# Controller.net
KiCad netlist of a schematic drawn in Altium Designer
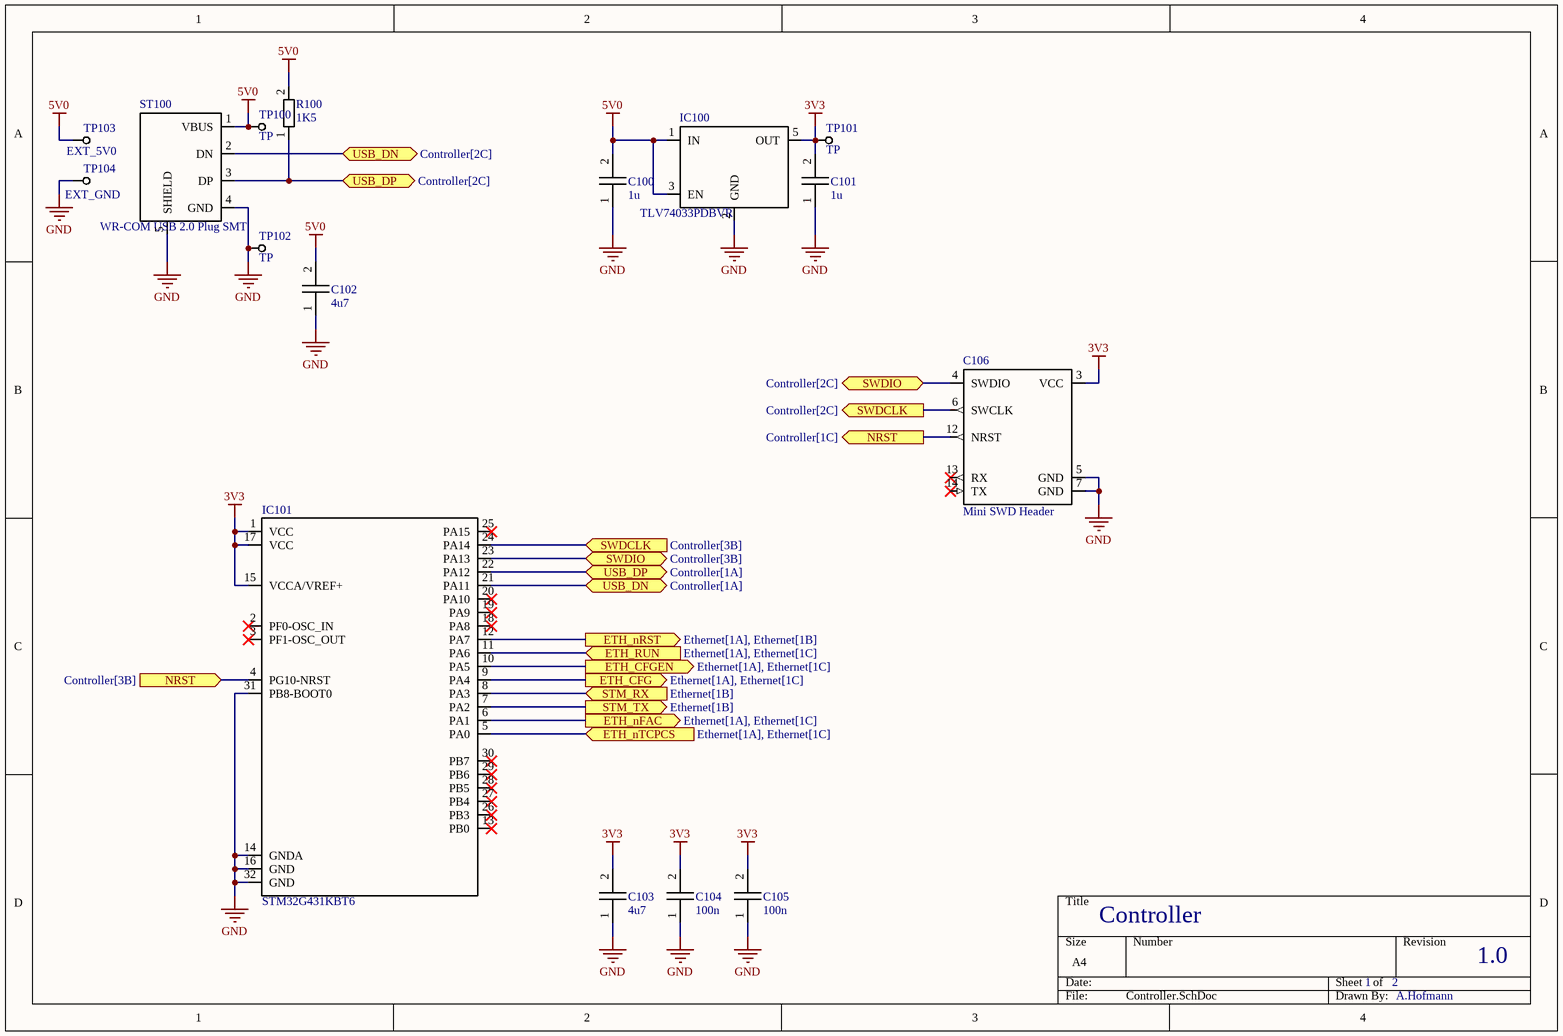
[diagram p0: Controller.SchDoc]

(export (version "E")
  (design (tool "Eeschema 10.0.6"))
  (components
    (comp (ref "C100") (value "1u") (footprint "C_0402") (libsource (lib "wol") (part "CeCa")))
    (comp (ref "C101") (value "1u") (footprint "C_0402") (libsource (lib "wol") (part "CeCa")))
    (comp (ref "C102") (value "4u7") (footprint "C_0603") (libsource (lib "wol") (part "CeCa")))
    (comp (ref "C103") (value "4u7") (footprint "C_0603") (libsource (lib "wol") (part "CeCa")))
    (comp (ref "C104") (value "100n") (footprint "C_0402") (libsource (lib "wol") (part "CeCa")))
    (comp (ref "C105") (value "100n") (footprint "C_0402") (libsource (lib "wol") (part "CeCa")))
    (comp (ref "C106")
      (value "Mini SWD Header")
      (footprint "Mini SWD Header")
      (libsource (lib "wol") (part "Mini SWD Header"))
    )
    (comp (ref "IC100")
      (value "TLV74033PDBVR")
      (footprint "SOT-23")
      (description "Linear Voltage Regulator IC Positive Fixed 1 Output 300mA SOT-23-5")
      (libsource (lib "wol") (part "TLV74033PDBVR"))
    )
    (comp (ref "IC101")
      (value "STM32G431KBT6")
      (footprint "LQFP32")
      (libsource (lib "wol") (part "STM32G431KBT6"))
    )
    (comp (ref "R100") (value "1K5") (footprint "R_0402") (libsource (lib "wol") (part "Res")))
    (comp (ref "ST100")
      (value "WR-COM USB 2.0 Plug SMT")
      (footprint "629004113921")
      (description "CONN PLUG USB2.0 TYPEA 4P SMD RA")
      (libsource (lib "wol") (part "WR-COM USB 2.0 Plug SMT"))
    )
    (comp (ref "TP100") (value "TP") (footprint "STP_0.5mm") (libsource (lib "wol") (part "TP")))
    (comp (ref "TP101") (value "TP") (footprint "STP_0.5mm") (libsource (lib "wol") (part "TP")))
    (comp (ref "TP102") (value "TP") (footprint "STP_0.5mm") (libsource (lib "wol") (part "TP")))
    (comp (ref "TP103") (value "EXT_5V0") (footprint "TTP_1mm") (libsource (lib "wol") (part "TP")))
    (comp (ref "TP104") (value "EXT_GND") (footprint "TTP_1mm") (libsource (lib "wol") (part "TP")))
  )
  (nets
    (net (code "1") (name "/ETH_CFG") (class "Default")
      (node (ref "IC101") (pin "9") (pinfunction "PA4_9") (pintype "bidirectional"))
    )
    (net (code "2") (name "/ETH_CFGEN") (class "Default")
      (node (ref "IC101") (pin "10") (pinfunction "PA5_10") (pintype "bidirectional"))
    )
    (net (code "3") (name "/ETH_RUN") (class "Default")
      (node (ref "IC101") (pin "11") (pinfunction "PA6_11") (pintype "bidirectional"))
    )
    (net (code "4") (name "/ETH_nFAC") (class "Default")
      (node (ref "IC101") (pin "6") (pinfunction "PA1_6") (pintype "bidirectional"))
    )
    (net (code "5") (name "/ETH_nRST") (class "Default")
      (node (ref "IC101") (pin "12") (pinfunction "PA7_12") (pintype "bidirectional"))
    )
    (net (code "6") (name "/ETH_nTCPCS") (class "Default")
      (node (ref "IC101") (pin "5") (pinfunction "PA0_5") (pintype "bidirectional"))
    )
    (net (code "7") (name "/NRST") (class "Default")
      (node (ref "C106") (pin "12") (pinfunction "NRST_12") (pintype "output"))
      (node (ref "IC101") (pin "4") (pinfunction "PG10-NRST_4") (pintype "bidirectional"))
    )
    (net (code "8") (name "/STM_RX") (class "Default")
      (node (ref "IC101") (pin "8") (pinfunction "PA3_8") (pintype "bidirectional"))
    )
    (net (code "9") (name "/STM_TX") (class "Default")
      (node (ref "IC101") (pin "7") (pinfunction "PA2_7") (pintype "bidirectional"))
    )
    (net (code "10") (name "/SWDCLK") (class "Default")
      (node (ref "C106") (pin "6") (pinfunction "SWCLK_6") (pintype "output"))
      (node (ref "IC101") (pin "24") (pinfunction "PA14_24") (pintype "bidirectional"))
    )
    (net (code "11") (name "/SWDIO") (class "Default")
      (node (ref "C106") (pin "4") (pinfunction "SWDIO_4") (pintype "bidirectional"))
      (node (ref "IC101") (pin "23") (pinfunction "PA13_23") (pintype "bidirectional"))
    )
    (net (code "12") (name "/USB_DN") (class "Default")
      (node (ref "IC101") (pin "21") (pinfunction "PA11_21") (pintype "bidirectional"))
      (node (ref "ST100") (pin "2") (pinfunction "DN_2") (pintype "bidirectional"))
    )
    (net (code "13") (name "/USB_DP") (class "Default")
      (node (ref "IC101") (pin "22") (pinfunction "PA12_22") (pintype "bidirectional"))
      (node (ref "R100") (pin "1") (pintype "passive"))
      (node (ref "ST100") (pin "3") (pinfunction "DP_3") (pintype "bidirectional"))
    )
    (net (code "14") (name "3V3") (class "Default")
      (node (ref "C101") (pin "2") (pintype "passive"))
      (node (ref "C103") (pin "2") (pintype "passive"))
      (node (ref "C104") (pin "2") (pintype "passive"))
      (node (ref "C105") (pin "2") (pintype "passive"))
      (node (ref "C106") (pin "3") (pinfunction "VCC_3") (pintype "power_in"))
      (node (ref "IC100") (pin "5") (pinfunction "OUT_5") (pintype "passive"))
      (node (ref "IC101") (pin "1") (pinfunction "VCC_1") (pintype "power_in"))
      (node (ref "IC101") (pin "15") (pinfunction "VCCA/VREF+_15") (pintype "power_in"))
      (node (ref "IC101") (pin "17") (pinfunction "VCC_17") (pintype "power_in"))
      (node (ref "TP101") (pin "1") (pintype "passive"))
    )
    (net (code "15") (name "5V0") (class "Default")
      (node (ref "C100") (pin "2") (pintype "passive"))
      (node (ref "C102") (pin "2") (pintype "passive"))
      (node (ref "IC100") (pin "1") (pinfunction "IN_1") (pintype "passive"))
      (node (ref "IC100") (pin "3") (pinfunction "EN_3") (pintype "passive"))
      (node (ref "R100") (pin "2") (pintype "passive"))
      (node (ref "ST100") (pin "1") (pinfunction "VBUS_1") (pintype "power_in"))
      (node (ref "TP100") (pin "1") (pintype "passive"))
      (node (ref "TP103") (pin "1") (pintype "passive"))
    )
    (net (code "16") (name "GND") (class "Default")
      (node (ref "C100") (pin "1") (pintype "passive"))
      (node (ref "C101") (pin "1") (pintype "passive"))
      (node (ref "C102") (pin "1") (pintype "passive"))
      (node (ref "C103") (pin "1") (pintype "passive"))
      (node (ref "C104") (pin "1") (pintype "passive"))
      (node (ref "C105") (pin "1") (pintype "passive"))
      (node (ref "C106") (pin "5") (pinfunction "GND_5") (pintype "power_in"))
      (node (ref "C106") (pin "7") (pinfunction "GND_7") (pintype "power_in"))
      (node (ref "IC100") (pin "2") (pinfunction "GND_2") (pintype "passive"))
      (node (ref "IC101") (pin "14") (pinfunction "GNDA_14") (pintype "power_in"))
      (node (ref "IC101") (pin "16") (pinfunction "GND_16") (pintype "power_in"))
      (node (ref "IC101") (pin "31") (pinfunction "PB8-BOOT0_31") (pintype "bidirectional"))
      (node (ref "IC101") (pin "32") (pinfunction "GND_32") (pintype "power_in"))
      (node (ref "ST100") (pin "4") (pinfunction "GND_4") (pintype "power_in"))
      (node (ref "ST100") (pin "5") (pinfunction "SHIELD_5") (pintype "power_in"))
      (node (ref "TP102") (pin "1") (pintype "passive"))
      (node (ref "TP104") (pin "1") (pintype "passive"))
    )
    (net (code "17") (name "unconnected-(C106-RX-Pad13)") (class "Default")
      (node (ref "C106") (pin "13") (pinfunction "RX_13") (pintype "output+no_connect"))
    )
    (net (code "18") (name "unconnected-(C106-TX-Pad14)") (class "Default")
      (node (ref "C106") (pin "14") (pinfunction "TX_14") (pintype "input+no_connect"))
    )
    (net (code "19") (name "unconnected-(IC101-PA8-Pad18)") (class "Default")
      (node (ref "IC101") (pin "18") (pinfunction "PA8_18") (pintype "bidirectional+no_connect"))
    )
    (net (code "20") (name "unconnected-(IC101-PA9-Pad19)") (class "Default")
      (node (ref "IC101") (pin "19") (pinfunction "PA9_19") (pintype "bidirectional+no_connect"))
    )
    (net (code "21") (name "unconnected-(IC101-PA10-Pad20)") (class "Default")
      (node (ref "IC101") (pin "20") (pinfunction "PA10_20") (pintype "bidirectional+no_connect"))
    )
    (net (code "22") (name "unconnected-(IC101-PA15-Pad25)") (class "Default")
      (node (ref "IC101") (pin "25") (pinfunction "PA15_25") (pintype "bidirectional+no_connect"))
    )
    (net (code "23") (name "unconnected-(IC101-PB0-Pad13)") (class "Default")
      (node (ref "IC101") (pin "13") (pinfunction "PB0_13") (pintype "bidirectional+no_connect"))
    )
    (net (code "24") (name "unconnected-(IC101-PB3-Pad26)") (class "Default")
      (node (ref "IC101") (pin "26") (pinfunction "PB3_26") (pintype "bidirectional+no_connect"))
    )
    (net (code "25") (name "unconnected-(IC101-PB4-Pad27)") (class "Default")
      (node (ref "IC101") (pin "27") (pinfunction "PB4_27") (pintype "bidirectional+no_connect"))
    )
    (net (code "26") (name "unconnected-(IC101-PB5-Pad28)") (class "Default")
      (node (ref "IC101") (pin "28") (pinfunction "PB5_28") (pintype "bidirectional+no_connect"))
    )
    (net (code "27") (name "unconnected-(IC101-PB6-Pad29)") (class "Default")
      (node (ref "IC101") (pin "29") (pinfunction "PB6_29") (pintype "bidirectional+no_connect"))
    )
    (net (code "28") (name "unconnected-(IC101-PB7-Pad30)") (class "Default")
      (node (ref "IC101") (pin "30") (pinfunction "PB7_30") (pintype "bidirectional+no_connect"))
    )
    (net (code "29") (name "unconnected-(IC101-PF0-OSC_IN-Pad2)") (class "Default")
      (node (ref "IC101") (pin "2") (pinfunction "PF0-OSC_IN_2") (pintype "bidirectional+no_connect"))
    )
    (net (code "30") (name "unconnected-(IC101-PF1-OSC_OUT-Pad3)") (class "Default")
      (node (ref "IC101") (pin "3") (pinfunction "PF1-OSC_OUT_3") (pintype "bidirectional+no_connect"))
    )
  )
)
